# board_1_7_FixMosfetGND_OUT12V_v.net
KiCad netlist of a schematic drawn in EAGLE
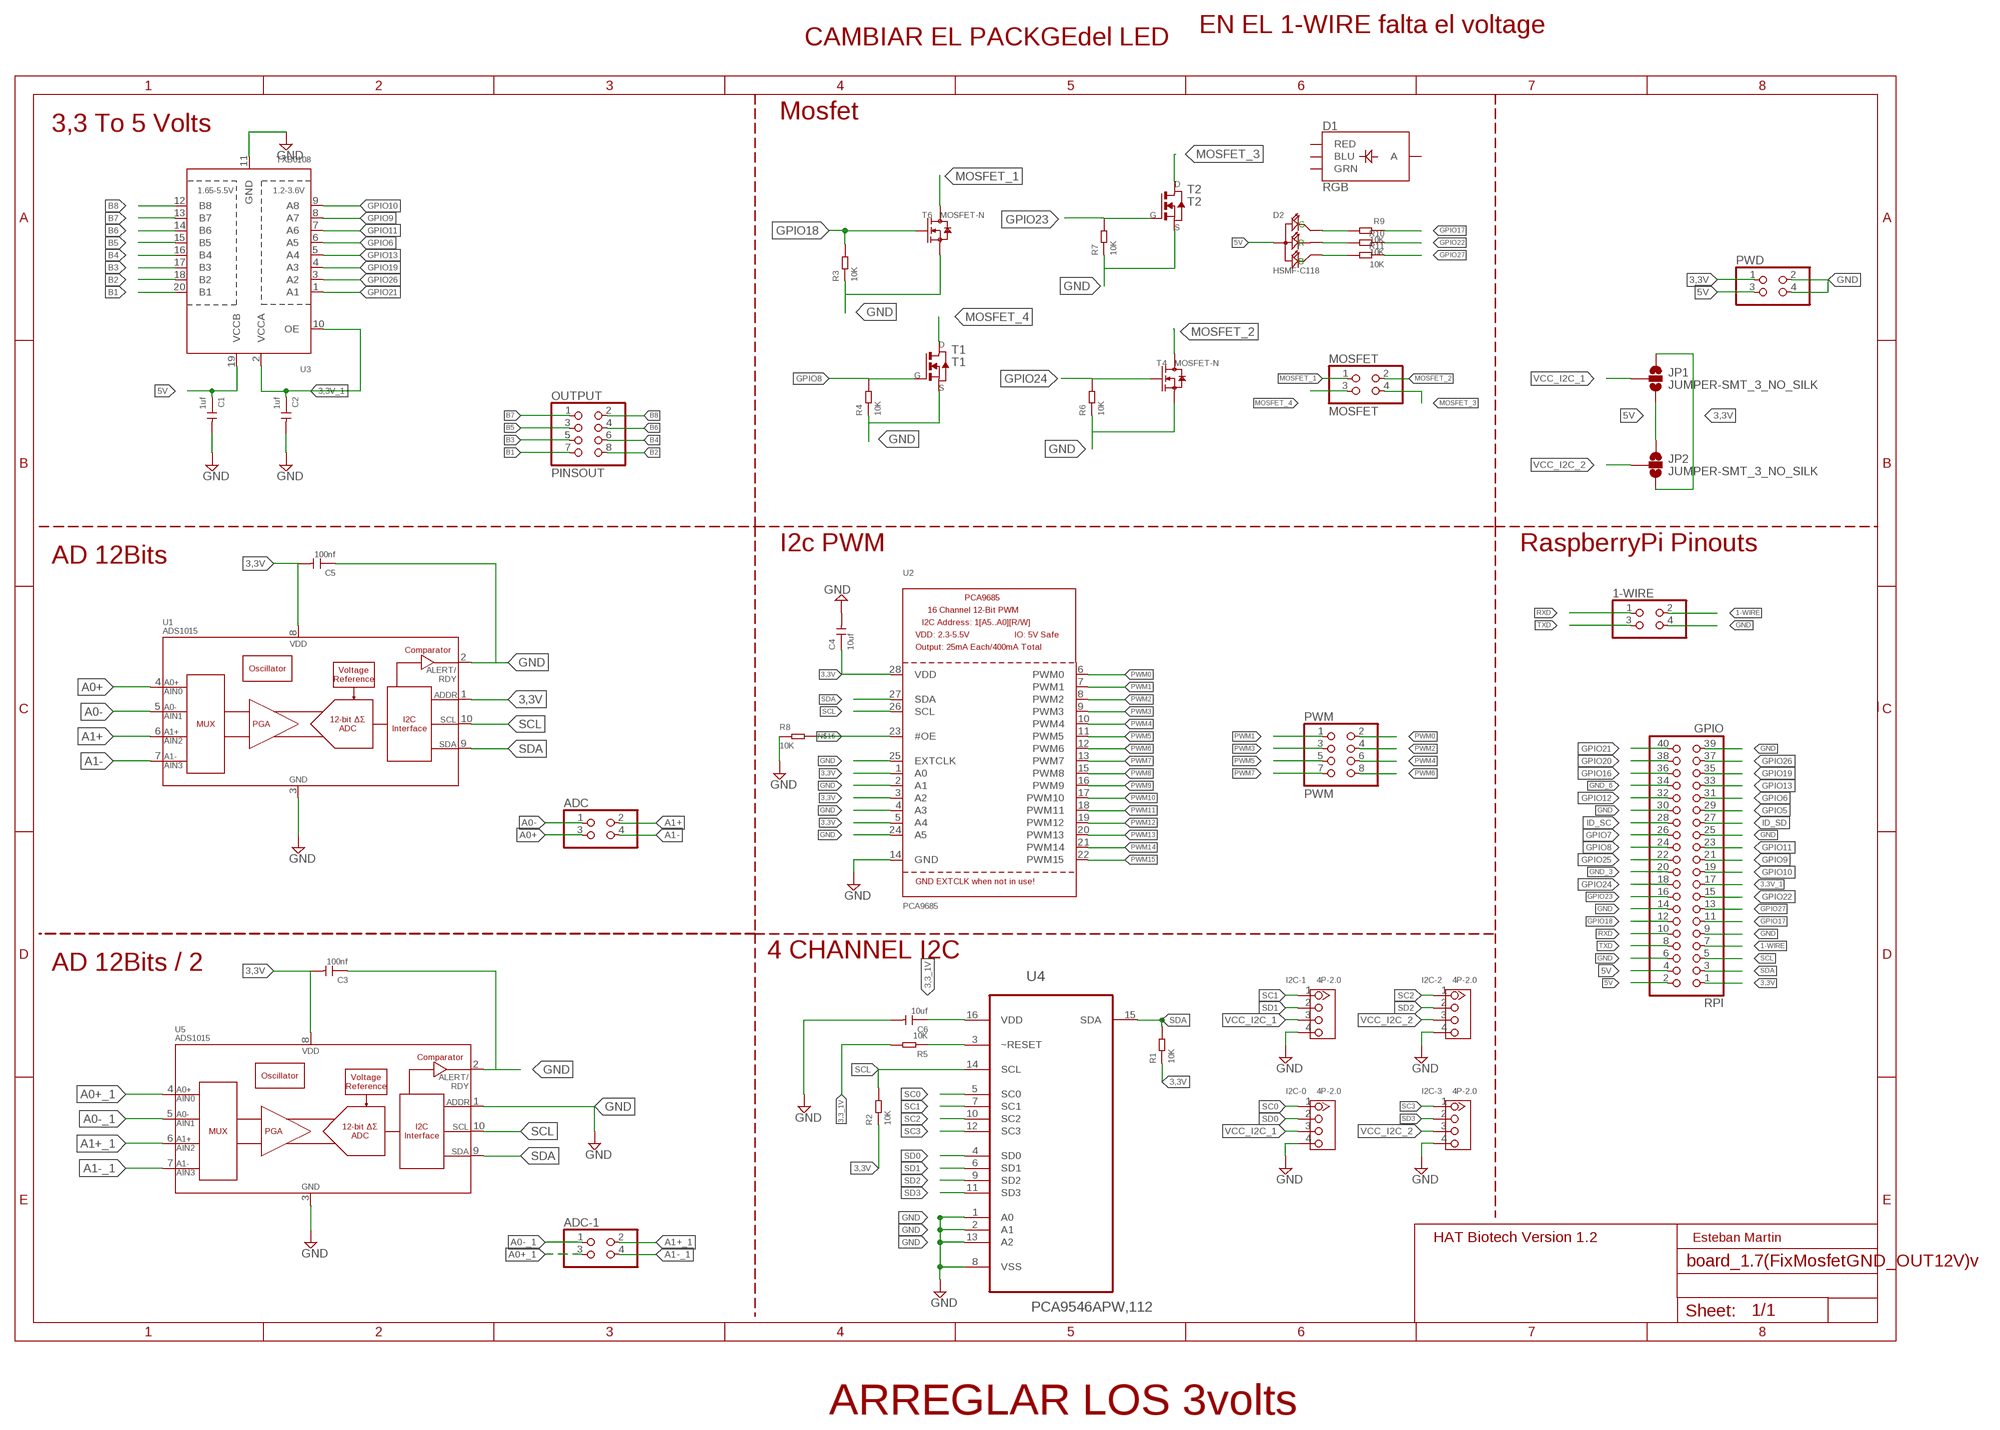
[diagram p0: schematic, sheet 1]

(export (version "E")
  (design (tool "Eeschema 10.0.6"))
  (components
    (comp (ref "1-WIRE")
      (value "PINHD-2X2")
      (footprint "eagle-import:2X02")
      (libsource (lib "eagle-import") (part "PINHD-2X2"))
    )
    (comp (ref "ADC")
      (value "PINHD-2X2")
      (footprint "eagle-import:2X02")
      (libsource (lib "eagle-import") (part "PINHD-2X2"))
    )
    (comp (ref "ADC-1")
      (value "PINHD-2X2")
      (footprint "eagle-import:2X02")
      (libsource (lib "eagle-import") (part "PINHD-2X2"))
    )
    (comp (ref "C1")
      (value "1uf")
      (footprint "eagle-import:C0805")
      (fields (field (name "MPN") "CC0805KKX7R8BB105"))
      (libsource (lib "eagle-import") (part "CERAMIC-1UF-25V-10%-X7R(0805)"))
    )
    (comp (ref "C2")
      (value "1uf")
      (footprint "eagle-import:C0805")
      (fields (field (name "MPN") "CC0805KKX7R8BB105"))
      (libsource (lib "eagle-import") (part "CERAMIC-1UF-25V-10%-X7R(0805)"))
    )
    (comp (ref "C3")
      (value "100nf")
      (footprint "eagle-import:C0805")
      (fields (field (name "MPN") "CC0805KRX7R9BB104"))
      (libsource (lib "eagle-import") (part "CERAMIC-100NF-50V-10%-X7R(0805)"))
    )
    (comp (ref "C4")
      (value "10uf")
      (footprint "eagle-import:C0805")
      (fields (field (name "MPN") "CC0805KKX7R8BB105"))
      (libsource (lib "eagle-import") (part "CERAMIC-1UF-25V-10%-X7R(0805)"))
    )
    (comp (ref "C5")
      (value "100nf")
      (footprint "eagle-import:C0805")
      (fields (field (name "MPN") "CC0805KRX7R9BB104"))
      (libsource (lib "eagle-import") (part "CERAMIC-100NF-50V-10%-X7R(0805)"))
    )
    (comp (ref "C6")
      (value "10uf")
      (footprint "eagle-import:C0805")
      (fields (field (name "MPN") "CC0805KKX7R8BB105"))
      (libsource (lib "eagle-import") (part "CERAMIC-1UF-25V-10%-X7R(0805)"))
    )
    (comp (ref "D1")
      (value "RGB")
      (footprint "eagle-import:P-LCC-4-3")
      (libsource (lib "eagle-import") (part "LED-RGB-CAPLCC"))
    )
    (comp (ref "D2")
      (value "HSMF-C118")
      (footprint "eagle-import:LED4-SMD-1210")
      (libsource (lib "eagle-import") (part "SMD-LED-RGB(4P-1210)"))
    )
    (comp (ref "I2C-0")
      (value "4P-2.0")
      (footprint "eagle-import:HW4-2.0")
      (libsource (lib "eagle-import") (part "GROVE-CONNECTOR-DIP(4P-2.0)"))
    )
    (comp (ref "I2C-1")
      (value "4P-2.0")
      (footprint "eagle-import:HW4-2.0")
      (libsource (lib "eagle-import") (part "GROVE-CONNECTOR-DIP(4P-2.0)"))
    )
    (comp (ref "I2C-2")
      (value "4P-2.0")
      (footprint "eagle-import:HW4-2.0")
      (libsource (lib "eagle-import") (part "GROVE-CONNECTOR-DIP(4P-2.0)"))
    )
    (comp (ref "I2C-3")
      (value "4P-2.0")
      (footprint "eagle-import:HW4-2.0")
      (libsource (lib "eagle-import") (part "GROVE-CONNECTOR-DIP(4P-2.0)"))
    )
    (comp (ref "JP1")
      (value "JUMPER-SMT_3_NO_SILK")
      (footprint "eagle-import:SMT-JUMPER_3_NO_SILK")
      (libsource (lib "eagle-import") (part "JUMPER-SMT_3_NO_SILK"))
    )
    (comp (ref "JP2")
      (value "JUMPER-SMT_3_NO_SILK")
      (footprint "eagle-import:SMT-JUMPER_3_NO_SILK")
      (libsource (lib "eagle-import") (part "JUMPER-SMT_3_NO_SILK"))
    )
    (comp (ref "MOSFET")
      (value "MOSFET")
      (footprint "eagle-import:2X02")
      (libsource (lib "eagle-import") (part "PINHD-2X2"))
    )
    (comp (ref "OUTPUT")
      (value "PINSOUT")
      (footprint "eagle-import:2X04")
      (libsource (lib "eagle-import") (part "PINHD-2X4"))
    )
    (comp (ref "PWD")
      (value "PINHD-2X2")
      (footprint "eagle-import:2X02")
      (libsource (lib "eagle-import") (part "PINHD-2X2"))
    )
    (comp (ref "PWM")
      (value "PWM")
      (footprint "eagle-import:2X04")
      (libsource (lib "eagle-import") (part "PINHD-2X4"))
    )
    (comp (ref "R1")
      (value "10K")
      (footprint "eagle-import:R0805")
      (fields (field (name "MPN") "RC0805FR-0710KL"))
      (libsource (lib "eagle-import") (part "SMD-RES-10K-1%-1/8W(0805)"))
    )
    (comp (ref "R2")
      (value "10K")
      (footprint "eagle-import:R0805")
      (fields (field (name "MPN") "RC0805FR-0710KL"))
      (libsource (lib "eagle-import") (part "SMD-RES-10K-1%-1/8W(0805)"))
    )
    (comp (ref "R3")
      (value "10K")
      (footprint "eagle-import:R0805")
      (fields (field (name "MPN") "RC0805FR-0710KL"))
      (libsource (lib "eagle-import") (part "SMD-RES-10K-1%-1/8W(0805)"))
    )
    (comp (ref "R4")
      (value "10K")
      (footprint "eagle-import:R0805")
      (fields (field (name "MPN") "RC0805FR-0710KL"))
      (libsource (lib "eagle-import") (part "SMD-RES-10K-1%-1/8W(0805)"))
    )
    (comp (ref "R5")
      (value "10K")
      (footprint "eagle-import:R0805")
      (fields (field (name "MPN") "RC0805FR-0710KL"))
      (libsource (lib "eagle-import") (part "SMD-RES-10K-1%-1/8W(0805)"))
    )
    (comp (ref "R6")
      (value "10K")
      (footprint "eagle-import:R0805")
      (fields (field (name "MPN") "RC0805FR-0710KL"))
      (libsource (lib "eagle-import") (part "SMD-RES-10K-1%-1/8W(0805)"))
    )
    (comp (ref "R7")
      (value "10K")
      (footprint "eagle-import:R0805")
      (fields (field (name "MPN") "RC0805FR-0710KL"))
      (libsource (lib "eagle-import") (part "SMD-RES-10K-1%-1/8W(0805)"))
    )
    (comp (ref "R8")
      (value "10K")
      (footprint "eagle-import:R0805")
      (fields (field (name "MPN") "RC0805FR-0710KL"))
      (libsource (lib "eagle-import") (part "SMD-RES-10K-1%-1/8W(0805)"))
    )
    (comp (ref "R9")
      (value "10K")
      (footprint "eagle-import:R0805")
      (fields (field (name "MPN") "RC0805FR-0710KL"))
      (libsource (lib "eagle-import") (part "SMD-RES-10K-1%-1/8W(0805)"))
    )
    (comp (ref "R10")
      (value "10K")
      (footprint "eagle-import:R0805")
      (fields (field (name "MPN") "RC0805FR-0710KL"))
      (libsource (lib "eagle-import") (part "SMD-RES-10K-1%-1/8W(0805)"))
    )
    (comp (ref "R11")
      (value "10K")
      (footprint "eagle-import:R0805")
      (fields (field (name "MPN") "RC0805FR-0710KL"))
      (libsource (lib "eagle-import") (part "SMD-RES-10K-1%-1/8W(0805)"))
    )
    (comp (ref "RPI")
      (value "GPIO")
      (footprint "eagle-import:2X20")
      (libsource (lib "eagle-import") (part "PINHD-2X20"))
    )
    (comp (ref "T1")
      (value "T1")
      (footprint "eagle-import:TO252")
      (libsource (lib "eagle-import") (part "NMOSFETTO252"))
    )
    (comp (ref "T2")
      (value "T2")
      (footprint "eagle-import:TO252")
      (libsource (lib "eagle-import") (part "NMOSFETTO252"))
    )
    (comp (ref "T4")
      (value "MOSFET-N")
      (footprint "eagle-import:SOT-23")
      (libsource (lib "eagle-import") (part "MOSFET-N"))
    )
    (comp (ref "T6")
      (value "MOSFET-N")
      (footprint "eagle-import:SOT-23")
      (libsource (lib "eagle-import") (part "MOSFET-N"))
    )
    (comp (ref "U1")
      (value "ADS1015")
      (footprint "eagle-import:MSOP10")
      (libsource (lib "eagle-import") (part "ADS1015"))
    )
    (comp (ref "U2")
      (value "PCA9685")
      (footprint "eagle-import:TSSOP28")
      (libsource (lib "eagle-import") (part "PCA9685"))
    )
    (comp (ref "U3")
      (value "TXB0108")
      (footprint "eagle-import:TSSOP20")
      (libsource (lib "eagle-import") (part "TXB0108PWR"))
    )
    (comp (ref "U4")
      (value "PCA9546APW,112")
      (footprint "eagle-import:SOP65P640X110-16N")
      (libsource (lib "eagle-import") (part "PCA9546APW,112"))
    )
    (comp (ref "U5")
      (value "ADS1015")
      (footprint "eagle-import:MSOP10")
      (libsource (lib "eagle-import") (part "ADS1015"))
    )
  )
  (nets
    (net (code "1") (name "1-WIRE") (class "Default")
      (node (ref "1-WIRE") (pin "2") (pinfunction "2_2") (pintype "passive"))
      (node (ref "RPI") (pin "7") (pinfunction "7_7") (pintype "passive"))
    )
    (net (code "2") (name "3,3V") (class "Default")
      (node (ref "C3") (pin "2") (pinfunction "2_2") (pintype "passive"))
      (node (ref "C4") (pin "1") (pinfunction "1_1") (pintype "passive"))
      (node (ref "C5") (pin "2") (pinfunction "2_2") (pintype "passive"))
      (node (ref "JP1") (pin "1") (pinfunction "1_1") (pintype "passive"))
      (node (ref "JP2") (pin "3") (pinfunction "3_3") (pintype "passive"))
      (node (ref "PWD") (pin "1") (pinfunction "1_1") (pintype "passive"))
      (node (ref "R1") (pin "1") (pinfunction "1_1") (pintype "passive"))
      (node (ref "R2") (pin "1") (pinfunction "1_1") (pintype "passive"))
      (node (ref "RPI") (pin "1") (pinfunction "1_1") (pintype "passive"))
      (node (ref "U1") (pin "1") (pinfunction "ADDR_1") (pintype "bidirectional"))
      (node (ref "U1") (pin "8") (pinfunction "VDD_8") (pintype "bidirectional"))
      (node (ref "U2") (pin "1") (pinfunction "A0_1") (pintype "bidirectional"))
      (node (ref "U2") (pin "28") (pinfunction "VDD_28") (pintype "power_in"))
      (node (ref "U2") (pin "3") (pinfunction "A2_3") (pintype "bidirectional"))
      (node (ref "U2") (pin "5") (pinfunction "A4_5") (pintype "bidirectional"))
      (node (ref "U5") (pin "8") (pinfunction "VDD_8") (pintype "bidirectional"))
    )
    (net (code "3") (name "3,3V_1") (class "Default")
      (node (ref "C2") (pin "1") (pinfunction "1_1") (pintype "passive"))
      (node (ref "RPI") (pin "17") (pinfunction "17_17") (pintype "passive"))
      (node (ref "U3") (pin "10") (pinfunction "OE_10") (pintype "bidirectional"))
      (node (ref "U3") (pin "2") (pinfunction "VCCA_2") (pintype "bidirectional"))
    )
    (net (code "4") (name "3,3_1V") (class "Default")
      (node (ref "C6") (pin "1") (pinfunction "1_1") (pintype "passive"))
      (node (ref "R5") (pin "2") (pinfunction "2_2") (pintype "passive"))
      (node (ref "U4") (pin "16") (pinfunction "VDD_16") (pintype "power_in"))
    )
    (net (code "5") (name "5V") (class "Default")
      (node (ref "C1") (pin "1") (pinfunction "1_1") (pintype "passive"))
      (node (ref "D2") (pin "1") (pinfunction "+_1") (pintype "bidirectional"))
      (node (ref "JP1") (pin "3") (pinfunction "3_3") (pintype "passive"))
      (node (ref "JP2") (pin "1") (pinfunction "1_1") (pintype "passive"))
      (node (ref "PWD") (pin "3") (pinfunction "3_3") (pintype "passive"))
      (node (ref "RPI") (pin "2") (pinfunction "2_2") (pintype "passive"))
      (node (ref "RPI") (pin "4") (pinfunction "4_4") (pintype "passive"))
      (node (ref "U3") (pin "19") (pinfunction "VCCB_19") (pintype "bidirectional"))
    )
    (net (code "6") (name "A0+") (class "Default")
      (node (ref "ADC") (pin "3") (pinfunction "3_3") (pintype "passive"))
      (node (ref "U1") (pin "4") (pinfunction "AIN0_4") (pintype "bidirectional"))
    )
    (net (code "7") (name "A0+_1") (class "Default")
      (node (ref "ADC-1") (pin "3") (pinfunction "3_3") (pintype "passive"))
      (node (ref "U5") (pin "4") (pinfunction "AIN0_4") (pintype "bidirectional"))
    )
    (net (code "8") (name "A0-") (class "Default")
      (node (ref "ADC") (pin "1") (pinfunction "1_1") (pintype "passive"))
      (node (ref "U1") (pin "5") (pinfunction "AIN1_5") (pintype "bidirectional"))
    )
    (net (code "9") (name "A0-_1") (class "Default")
      (node (ref "ADC-1") (pin "1") (pinfunction "1_1") (pintype "passive"))
      (node (ref "U5") (pin "5") (pinfunction "AIN1_5") (pintype "bidirectional"))
    )
    (net (code "10") (name "A1+") (class "Default")
      (node (ref "ADC") (pin "2") (pinfunction "2_2") (pintype "passive"))
      (node (ref "U1") (pin "6") (pinfunction "AIN2_6") (pintype "bidirectional"))
    )
    (net (code "11") (name "A1+_1") (class "Default")
      (node (ref "ADC-1") (pin "2") (pinfunction "2_2") (pintype "passive"))
      (node (ref "U5") (pin "6") (pinfunction "AIN2_6") (pintype "bidirectional"))
    )
    (net (code "12") (name "A1-") (class "Default")
      (node (ref "ADC") (pin "4") (pinfunction "4_4") (pintype "passive"))
      (node (ref "U1") (pin "7") (pinfunction "AIN3_7") (pintype "bidirectional"))
    )
    (net (code "13") (name "A1-_1") (class "Default")
      (node (ref "ADC-1") (pin "4") (pinfunction "4_4") (pintype "passive"))
      (node (ref "U5") (pin "7") (pinfunction "AIN3_7") (pintype "bidirectional"))
    )
    (net (code "14") (name "B1") (class "Default")
      (node (ref "OUTPUT") (pin "7") (pinfunction "7_7") (pintype "passive"))
      (node (ref "U3") (pin "20") (pinfunction "B1_20") (pintype "bidirectional"))
    )
    (net (code "15") (name "B2") (class "Default")
      (node (ref "OUTPUT") (pin "8") (pinfunction "8_8") (pintype "passive"))
      (node (ref "U3") (pin "18") (pinfunction "B2_18") (pintype "bidirectional"))
    )
    (net (code "16") (name "B3") (class "Default")
      (node (ref "OUTPUT") (pin "5") (pinfunction "5_5") (pintype "passive"))
      (node (ref "U3") (pin "17") (pinfunction "B3_17") (pintype "bidirectional"))
    )
    (net (code "17") (name "B4") (class "Default")
      (node (ref "OUTPUT") (pin "6") (pinfunction "6_6") (pintype "passive"))
      (node (ref "U3") (pin "16") (pinfunction "B4_16") (pintype "bidirectional"))
    )
    (net (code "18") (name "B5") (class "Default")
      (node (ref "OUTPUT") (pin "3") (pinfunction "3_3") (pintype "passive"))
      (node (ref "U3") (pin "15") (pinfunction "B5_15") (pintype "bidirectional"))
    )
    (net (code "19") (name "B6") (class "Default")
      (node (ref "OUTPUT") (pin "4") (pinfunction "4_4") (pintype "passive"))
      (node (ref "U3") (pin "14") (pinfunction "B6_14") (pintype "bidirectional"))
    )
    (net (code "20") (name "B7") (class "Default")
      (node (ref "OUTPUT") (pin "1") (pinfunction "1_1") (pintype "passive"))
      (node (ref "U3") (pin "13") (pinfunction "B7_13") (pintype "bidirectional"))
    )
    (net (code "21") (name "B8") (class "Default")
      (node (ref "OUTPUT") (pin "2") (pinfunction "2_2") (pintype "passive"))
      (node (ref "U3") (pin "12") (pinfunction "B8_12") (pintype "bidirectional"))
    )
    (net (code "22") (name "GND") (class "Default")
      (node (ref "1-WIRE") (pin "4") (pinfunction "4_4") (pintype "passive"))
      (node (ref "C1") (pin "2") (pinfunction "2_2") (pintype "passive"))
      (node (ref "C2") (pin "2") (pinfunction "2_2") (pintype "passive"))
      (node (ref "C3") (pin "1") (pinfunction "1_1") (pintype "passive"))
      (node (ref "C4") (pin "2") (pinfunction "2_2") (pintype "passive"))
      (node (ref "C5") (pin "1") (pinfunction "1_1") (pintype "passive"))
      (node (ref "C6") (pin "2") (pinfunction "2_2") (pintype "passive"))
      (node (ref "I2C-0") (pin "4") (pinfunction "4_4") (pintype "bidirectional"))
      (node (ref "I2C-1") (pin "4") (pinfunction "4_4") (pintype "bidirectional"))
      (node (ref "I2C-2") (pin "4") (pinfunction "4_4") (pintype "bidirectional"))
      (node (ref "I2C-3") (pin "4") (pinfunction "4_4") (pintype "bidirectional"))
      (node (ref "PWD") (pin "2") (pinfunction "2_2") (pintype "passive"))
      (node (ref "PWD") (pin "4") (pinfunction "4_4") (pintype "passive"))
      (node (ref "R3") (pin "1") (pinfunction "1_1") (pintype "passive"))
      (node (ref "R4") (pin "1") (pinfunction "1_1") (pintype "passive"))
      (node (ref "R6") (pin "1") (pinfunction "1_1") (pintype "passive"))
      (node (ref "R7") (pin "1") (pinfunction "1_1") (pintype "passive"))
      (node (ref "R8") (pin "1") (pinfunction "1_1") (pintype "passive"))
      (node (ref "RPI") (pin "14") (pinfunction "14_14") (pintype "passive"))
      (node (ref "RPI") (pin "25") (pinfunction "25_25") (pintype "passive"))
      (node (ref "RPI") (pin "30") (pinfunction "30_30") (pintype "passive"))
      (node (ref "RPI") (pin "39") (pinfunction "39_39") (pintype "passive"))
      (node (ref "RPI") (pin "6") (pinfunction "6_6") (pintype "passive"))
      (node (ref "RPI") (pin "9") (pinfunction "9_9") (pintype "passive"))
      (node (ref "T1") (pin "2") (pinfunction "S_2") (pintype "passive"))
      (node (ref "T2") (pin "2") (pinfunction "S_2") (pintype "passive"))
      (node (ref "T4") (pin "2") (pinfunction "S_2") (pintype "passive"))
      (node (ref "T6") (pin "2") (pinfunction "S_2") (pintype "passive"))
      (node (ref "U1") (pin "2") (pinfunction "ALERT/RDY_2") (pintype "bidirectional"))
      (node (ref "U1") (pin "3") (pinfunction "VSS_3") (pintype "bidirectional"))
      (node (ref "U2") (pin "14") (pinfunction "GND_14") (pintype "power_in"))
      (node (ref "U2") (pin "2") (pinfunction "A1_2") (pintype "bidirectional"))
      (node (ref "U2") (pin "24") (pinfunction "A5_24") (pintype "bidirectional"))
      (node (ref "U2") (pin "25") (pinfunction "EXTCLK_25") (pintype "input"))
      (node (ref "U2") (pin "4") (pinfunction "A3_4") (pintype "bidirectional"))
      (node (ref "U3") (pin "11") (pinfunction "GND_11") (pintype "bidirectional"))
      (node (ref "U4") (pin "1") (pinfunction "A0_1") (pintype "input"))
      (node (ref "U4") (pin "13") (pinfunction "A2_13") (pintype "input"))
      (node (ref "U4") (pin "2") (pinfunction "A1_2") (pintype "input"))
      (node (ref "U4") (pin "8") (pinfunction "VSS_8") (pintype "passive"))
      (node (ref "U5") (pin "1") (pinfunction "ADDR_1") (pintype "bidirectional"))
      (node (ref "U5") (pin "2") (pinfunction "ALERT/RDY_2") (pintype "bidirectional"))
      (node (ref "U5") (pin "3") (pinfunction "VSS_3") (pintype "bidirectional"))
    )
    (net (code "23") (name "GND_3") (class "Default")
      (node (ref "RPI") (pin "20") (pinfunction "20_20") (pintype "passive"))
    )
    (net (code "24") (name "GND_6") (class "Default")
      (node (ref "RPI") (pin "34") (pinfunction "34_34") (pintype "passive"))
    )
    (net (code "25") (name "GPIO5") (class "Default")
      (node (ref "RPI") (pin "29") (pinfunction "29_29") (pintype "passive"))
    )
    (net (code "26") (name "GPIO6") (class "Default")
      (node (ref "RPI") (pin "31") (pinfunction "31_31") (pintype "passive"))
      (node (ref "U3") (pin "6") (pinfunction "A5_6") (pintype "bidirectional"))
    )
    (net (code "27") (name "GPIO7") (class "Default")
      (node (ref "RPI") (pin "26") (pinfunction "26_26") (pintype "passive"))
    )
    (net (code "28") (name "GPIO8") (class "Default")
      (node (ref "R4") (pin "2") (pinfunction "2_2") (pintype "passive"))
      (node (ref "RPI") (pin "24") (pinfunction "24_24") (pintype "passive"))
      (node (ref "T1") (pin "1") (pinfunction "G_1") (pintype "passive"))
    )
    (net (code "29") (name "GPIO9") (class "Default")
      (node (ref "RPI") (pin "21") (pinfunction "21_21") (pintype "passive"))
      (node (ref "U3") (pin "8") (pinfunction "A7_8") (pintype "bidirectional"))
    )
    (net (code "30") (name "GPIO10") (class "Default")
      (node (ref "RPI") (pin "19") (pinfunction "19_19") (pintype "passive"))
      (node (ref "U3") (pin "9") (pinfunction "A8_9") (pintype "bidirectional"))
    )
    (net (code "31") (name "GPIO11") (class "Default")
      (node (ref "RPI") (pin "23") (pinfunction "23_23") (pintype "passive"))
      (node (ref "U3") (pin "7") (pinfunction "A6_7") (pintype "bidirectional"))
    )
    (net (code "32") (name "GPIO12") (class "Default")
      (node (ref "RPI") (pin "32") (pinfunction "32_32") (pintype "passive"))
    )
    (net (code "33") (name "GPIO13") (class "Default")
      (node (ref "RPI") (pin "33") (pinfunction "33_33") (pintype "passive"))
      (node (ref "U3") (pin "5") (pinfunction "A4_5") (pintype "bidirectional"))
    )
    (net (code "34") (name "GPIO16") (class "Default")
      (node (ref "RPI") (pin "36") (pinfunction "36_36") (pintype "passive"))
    )
    (net (code "35") (name "GPIO17") (class "Default")
      (node (ref "R9") (pin "1") (pinfunction "1_1") (pintype "passive"))
      (node (ref "RPI") (pin "11") (pinfunction "11_11") (pintype "passive"))
    )
    (net (code "36") (name "GPIO18") (class "Default")
      (node (ref "R3") (pin "2") (pinfunction "2_2") (pintype "passive"))
      (node (ref "RPI") (pin "12") (pinfunction "12_12") (pintype "passive"))
      (node (ref "T6") (pin "1") (pinfunction "G_1") (pintype "passive"))
    )
    (net (code "37") (name "GPIO19") (class "Default")
      (node (ref "RPI") (pin "35") (pinfunction "35_35") (pintype "passive"))
      (node (ref "U3") (pin "4") (pinfunction "A3_4") (pintype "bidirectional"))
    )
    (net (code "38") (name "GPIO20") (class "Default")
      (node (ref "RPI") (pin "38") (pinfunction "38_38") (pintype "passive"))
    )
    (net (code "39") (name "GPIO21") (class "Default")
      (node (ref "RPI") (pin "40") (pinfunction "40_40") (pintype "passive"))
      (node (ref "U3") (pin "1") (pinfunction "A1_1") (pintype "bidirectional"))
    )
    (net (code "40") (name "GPIO22") (class "Default")
      (node (ref "R10") (pin "1") (pinfunction "1_1") (pintype "passive"))
      (node (ref "RPI") (pin "15") (pinfunction "15_15") (pintype "passive"))
    )
    (net (code "41") (name "GPIO23") (class "Default")
      (node (ref "R7") (pin "2") (pinfunction "2_2") (pintype "passive"))
      (node (ref "RPI") (pin "16") (pinfunction "16_16") (pintype "passive"))
      (node (ref "T2") (pin "1") (pinfunction "G_1") (pintype "passive"))
    )
    (net (code "42") (name "GPIO24") (class "Default")
      (node (ref "R6") (pin "2") (pinfunction "2_2") (pintype "passive"))
      (node (ref "RPI") (pin "18") (pinfunction "18_18") (pintype "passive"))
      (node (ref "T4") (pin "1") (pinfunction "G_1") (pintype "passive"))
    )
    (net (code "43") (name "GPIO25") (class "Default")
      (node (ref "RPI") (pin "22") (pinfunction "22_22") (pintype "passive"))
    )
    (net (code "44") (name "GPIO26") (class "Default")
      (node (ref "RPI") (pin "37") (pinfunction "37_37") (pintype "passive"))
      (node (ref "U3") (pin "3") (pinfunction "A2_3") (pintype "bidirectional"))
    )
    (net (code "45") (name "GPIO27") (class "Default")
      (node (ref "R11") (pin "1") (pinfunction "1_1") (pintype "passive"))
      (node (ref "RPI") (pin "13") (pinfunction "13_13") (pintype "passive"))
    )
    (net (code "46") (name "ID_SC") (class "Default")
      (node (ref "RPI") (pin "28") (pinfunction "28_28") (pintype "passive"))
    )
    (net (code "47") (name "ID_SD") (class "Default")
      (node (ref "RPI") (pin "27") (pinfunction "27_27") (pintype "passive"))
    )
    (net (code "48") (name "MOSFET_1") (class "Default")
      (node (ref "MOSFET") (pin "1") (pinfunction "1_1") (pintype "passive"))
      (node (ref "T6") (pin "3") (pinfunction "D_3") (pintype "passive"))
    )
    (net (code "49") (name "MOSFET_2") (class "Default")
      (node (ref "MOSFET") (pin "2") (pinfunction "2_2") (pintype "passive"))
      (node (ref "T4") (pin "3") (pinfunction "D_3") (pintype "passive"))
    )
    (net (code "50") (name "MOSFET_3") (class "Default")
      (node (ref "MOSFET") (pin "4") (pinfunction "4_4") (pintype "passive"))
      (node (ref "T2") (pin "3") (pinfunction "D_3") (pintype "passive"))
    )
    (net (code "51") (name "MOSFET_4") (class "Default")
      (node (ref "MOSFET") (pin "3") (pinfunction "3_3") (pintype "passive"))
      (node (ref "T1") (pin "3") (pinfunction "D_3") (pintype "passive"))
    )
    (net (code "52") (name "N$16") (class "Default")
      (node (ref "R8") (pin "2") (pinfunction "2_2") (pintype "passive"))
      (node (ref "U2") (pin "23") (pinfunction "#OE_23") (pintype "input"))
    )
    (net (code "53") (name "Net-(D2-B)") (class "Default")
      (node (ref "D2") (pin "4") (pinfunction "B_4") (pintype "bidirectional"))
      (node (ref "R11") (pin "2") (pinfunction "2_2") (pintype "passive"))
    )
    (net (code "54") (name "Net-(D2-G)") (class "Default")
      (node (ref "D2") (pin "3") (pinfunction "G_3") (pintype "bidirectional"))
      (node (ref "R9") (pin "2") (pinfunction "2_2") (pintype "passive"))
    )
    (net (code "55") (name "Net-(D2-R)") (class "Default")
      (node (ref "D2") (pin "2") (pinfunction "R_2") (pintype "bidirectional"))
      (node (ref "R10") (pin "2") (pinfunction "2_2") (pintype "passive"))
    )
    (net (code "56") (name "Net-(U4-~{RESET})") (class "Default")
      (node (ref "R5") (pin "1") (pinfunction "1_1") (pintype "passive"))
      (node (ref "U4") (pin "3") (pinfunction "~{RESET}_3") (pintype "input"))
    )
    (net (code "57") (name "PWM0") (class "Default")
      (node (ref "PWM") (pin "2") (pinfunction "2_2") (pintype "passive"))
      (node (ref "U2") (pin "6") (pinfunction "PWM0_6") (pintype "output"))
    )
    (net (code "58") (name "PWM1") (class "Default")
      (node (ref "PWM") (pin "1") (pinfunction "1_1") (pintype "passive"))
      (node (ref "U2") (pin "7") (pinfunction "PWM1_7") (pintype "output"))
    )
    (net (code "59") (name "PWM2") (class "Default")
      (node (ref "PWM") (pin "4") (pinfunction "4_4") (pintype "passive"))
      (node (ref "U2") (pin "8") (pinfunction "PWM2_8") (pintype "output"))
    )
    (net (code "60") (name "PWM3") (class "Default")
      (node (ref "PWM") (pin "3") (pinfunction "3_3") (pintype "passive"))
      (node (ref "U2") (pin "9") (pinfunction "PWM3_9") (pintype "output"))
    )
    (net (code "61") (name "PWM4") (class "Default")
      (node (ref "PWM") (pin "6") (pinfunction "6_6") (pintype "passive"))
      (node (ref "U2") (pin "10") (pinfunction "PWM4_10") (pintype "output"))
    )
    (net (code "62") (name "PWM5") (class "Default")
      (node (ref "PWM") (pin "5") (pinfunction "5_5") (pintype "passive"))
      (node (ref "U2") (pin "11") (pinfunction "PWM5_11") (pintype "output"))
    )
    (net (code "63") (name "PWM6") (class "Default")
      (node (ref "PWM") (pin "8") (pinfunction "8_8") (pintype "passive"))
      (node (ref "U2") (pin "12") (pinfunction "PWM6_12") (pintype "output"))
    )
    (net (code "64") (name "PWM7") (class "Default")
      (node (ref "PWM") (pin "7") (pinfunction "7_7") (pintype "passive"))
      (node (ref "U2") (pin "13") (pinfunction "PWM7_13") (pintype "output"))
    )
    (net (code "65") (name "PWM8") (class "Default")
      (node (ref "U2") (pin "15") (pinfunction "PWM8_15") (pintype "output"))
    )
    (net (code "66") (name "PWM9") (class "Default")
      (node (ref "U2") (pin "16") (pinfunction "PWM9_16") (pintype "output"))
    )
    (net (code "67") (name "PWM10") (class "Default")
      (node (ref "U2") (pin "17") (pinfunction "PWM10_17") (pintype "output"))
    )
    (net (code "68") (name "PWM11") (class "Default")
      (node (ref "U2") (pin "18") (pinfunction "PWM11_18") (pintype "output"))
    )
    (net (code "69") (name "PWM12") (class "Default")
      (node (ref "U2") (pin "19") (pinfunction "PWM12_19") (pintype "output"))
    )
    (net (code "70") (name "PWM13") (class "Default")
      (node (ref "U2") (pin "20") (pinfunction "PWM13_20") (pintype "output"))
    )
    (net (code "71") (name "PWM14") (class "Default")
      (node (ref "U2") (pin "21") (pinfunction "PWM14_21") (pintype "output"))
    )
    (net (code "72") (name "PWM15") (class "Default")
      (node (ref "U2") (pin "22") (pinfunction "PWM15_22") (pintype "output"))
    )
    (net (code "73") (name "RXD") (class "Default")
      (node (ref "1-WIRE") (pin "1") (pinfunction "1_1") (pintype "passive"))
      (node (ref "RPI") (pin "10") (pinfunction "10_10") (pintype "passive"))
    )
    (net (code "74") (name "SC0") (class "Default")
      (node (ref "I2C-0") (pin "1") (pinfunction "1_1") (pintype "bidirectional"))
      (node (ref "U4") (pin "5") (pinfunction "SC0_5") (pintype "input"))
    )
    (net (code "75") (name "SC1") (class "Default")
      (node (ref "I2C-1") (pin "1") (pinfunction "1_1") (pintype "bidirectional"))
      (node (ref "U4") (pin "7") (pinfunction "SC1_7") (pintype "input"))
    )
    (net (code "76") (name "SC2") (class "Default")
      (node (ref "I2C-2") (pin "1") (pinfunction "1_1") (pintype "bidirectional"))
      (node (ref "U4") (pin "10") (pinfunction "SC2_10") (pintype "input"))
    )
    (net (code "77") (name "SC3") (class "Default")
      (node (ref "I2C-3") (pin "1") (pinfunction "1_1") (pintype "bidirectional"))
      (node (ref "U4") (pin "12") (pinfunction "SC3_12") (pintype "input"))
    )
    (net (code "78") (name "SCL") (class "Default")
      (node (ref "R2") (pin "2") (pinfunction "2_2") (pintype "passive"))
      (node (ref "RPI") (pin "5") (pinfunction "5_5") (pintype "passive"))
      (node (ref "U1") (pin "10") (pinfunction "SCL_10") (pintype "bidirectional"))
      (node (ref "U2") (pin "26") (pinfunction "SCL_26") (pintype "bidirectional"))
      (node (ref "U4") (pin "14") (pinfunction "SCL_14") (pintype "bidirectional"))
      (node (ref "U5") (pin "10") (pinfunction "SCL_10") (pintype "bidirectional"))
    )
    (net (code "79") (name "SD0") (class "Default")
      (node (ref "I2C-0") (pin "2") (pinfunction "2_2") (pintype "bidirectional"))
      (node (ref "U4") (pin "4") (pinfunction "SD0_4") (pintype "input"))
    )
    (net (code "80") (name "SD1") (class "Default")
      (node (ref "I2C-1") (pin "2") (pinfunction "2_2") (pintype "bidirectional"))
      (node (ref "U4") (pin "6") (pinfunction "SD1_6") (pintype "input"))
    )
    (net (code "81") (name "SD2") (class "Default")
      (node (ref "I2C-2") (pin "2") (pinfunction "2_2") (pintype "bidirectional"))
      (node (ref "U4") (pin "9") (pinfunction "SD2_9") (pintype "input"))
    )
    (net (code "82") (name "SD3") (class "Default")
      (node (ref "I2C-3") (pin "2") (pinfunction "2_2") (pintype "bidirectional"))
      (node (ref "U4") (pin "11") (pinfunction "SD3_11") (pintype "input"))
    )
    (net (code "83") (name "SDA") (class "Default")
      (node (ref "R1") (pin "2") (pinfunction "2_2") (pintype "passive"))
      (node (ref "RPI") (pin "3") (pinfunction "3_3") (pintype "passive"))
      (node (ref "U1") (pin "9") (pinfunction "SDA_9") (pintype "bidirectional"))
      (node (ref "U2") (pin "27") (pinfunction "SDA_27") (pintype "bidirectional"))
      (node (ref "U4") (pin "15") (pinfunction "SDA_15") (pintype "bidirectional"))
      (node (ref "U5") (pin "9") (pinfunction "SDA_9") (pintype "bidirectional"))
    )
    (net (code "84") (name "TXD") (class "Default")
      (node (ref "1-WIRE") (pin "3") (pinfunction "3_3") (pintype "passive"))
      (node (ref "RPI") (pin "8") (pinfunction "8_8") (pintype "passive"))
    )
    (net (code "85") (name "VCC_I2C_1") (class "Default")
      (node (ref "I2C-0") (pin "3") (pinfunction "3_3") (pintype "bidirectional"))
      (node (ref "I2C-1") (pin "3") (pinfunction "3_3") (pintype "bidirectional"))
      (node (ref "JP1") (pin "2") (pinfunction "2_2") (pintype "passive"))
    )
    (net (code "86") (name "VCC_I2C_2") (class "Default")
      (node (ref "I2C-2") (pin "3") (pinfunction "3_3") (pintype "bidirectional"))
      (node (ref "I2C-3") (pin "3") (pinfunction "3_3") (pintype "bidirectional"))
      (node (ref "JP2") (pin "2") (pinfunction "2_2") (pintype "passive"))
    )
    (net (code "87") (name "unconnected-(D1-A-Pad4)") (class "Default")
      (node (ref "D1") (pin "4") (pinfunction "A_4") (pintype "bidirectional"))
    )
    (net (code "88") (name "unconnected-(D1-BLU-Pad3)") (class "Default")
      (node (ref "D1") (pin "3") (pinfunction "BLU_3") (pintype "bidirectional"))
    )
    (net (code "89") (name "unconnected-(D1-GRN-Pad2)") (class "Default")
      (node (ref "D1") (pin "2") (pinfunction "GRN_2") (pintype "bidirectional"))
    )
    (net (code "90") (name "unconnected-(D1-RED-Pad1)") (class "Default")
      (node (ref "D1") (pin "1") (pinfunction "RED_1") (pintype "bidirectional"))
    )
  )
)
